# Controller.net
KiCad netlist of a schematic drawn in Altium Designer
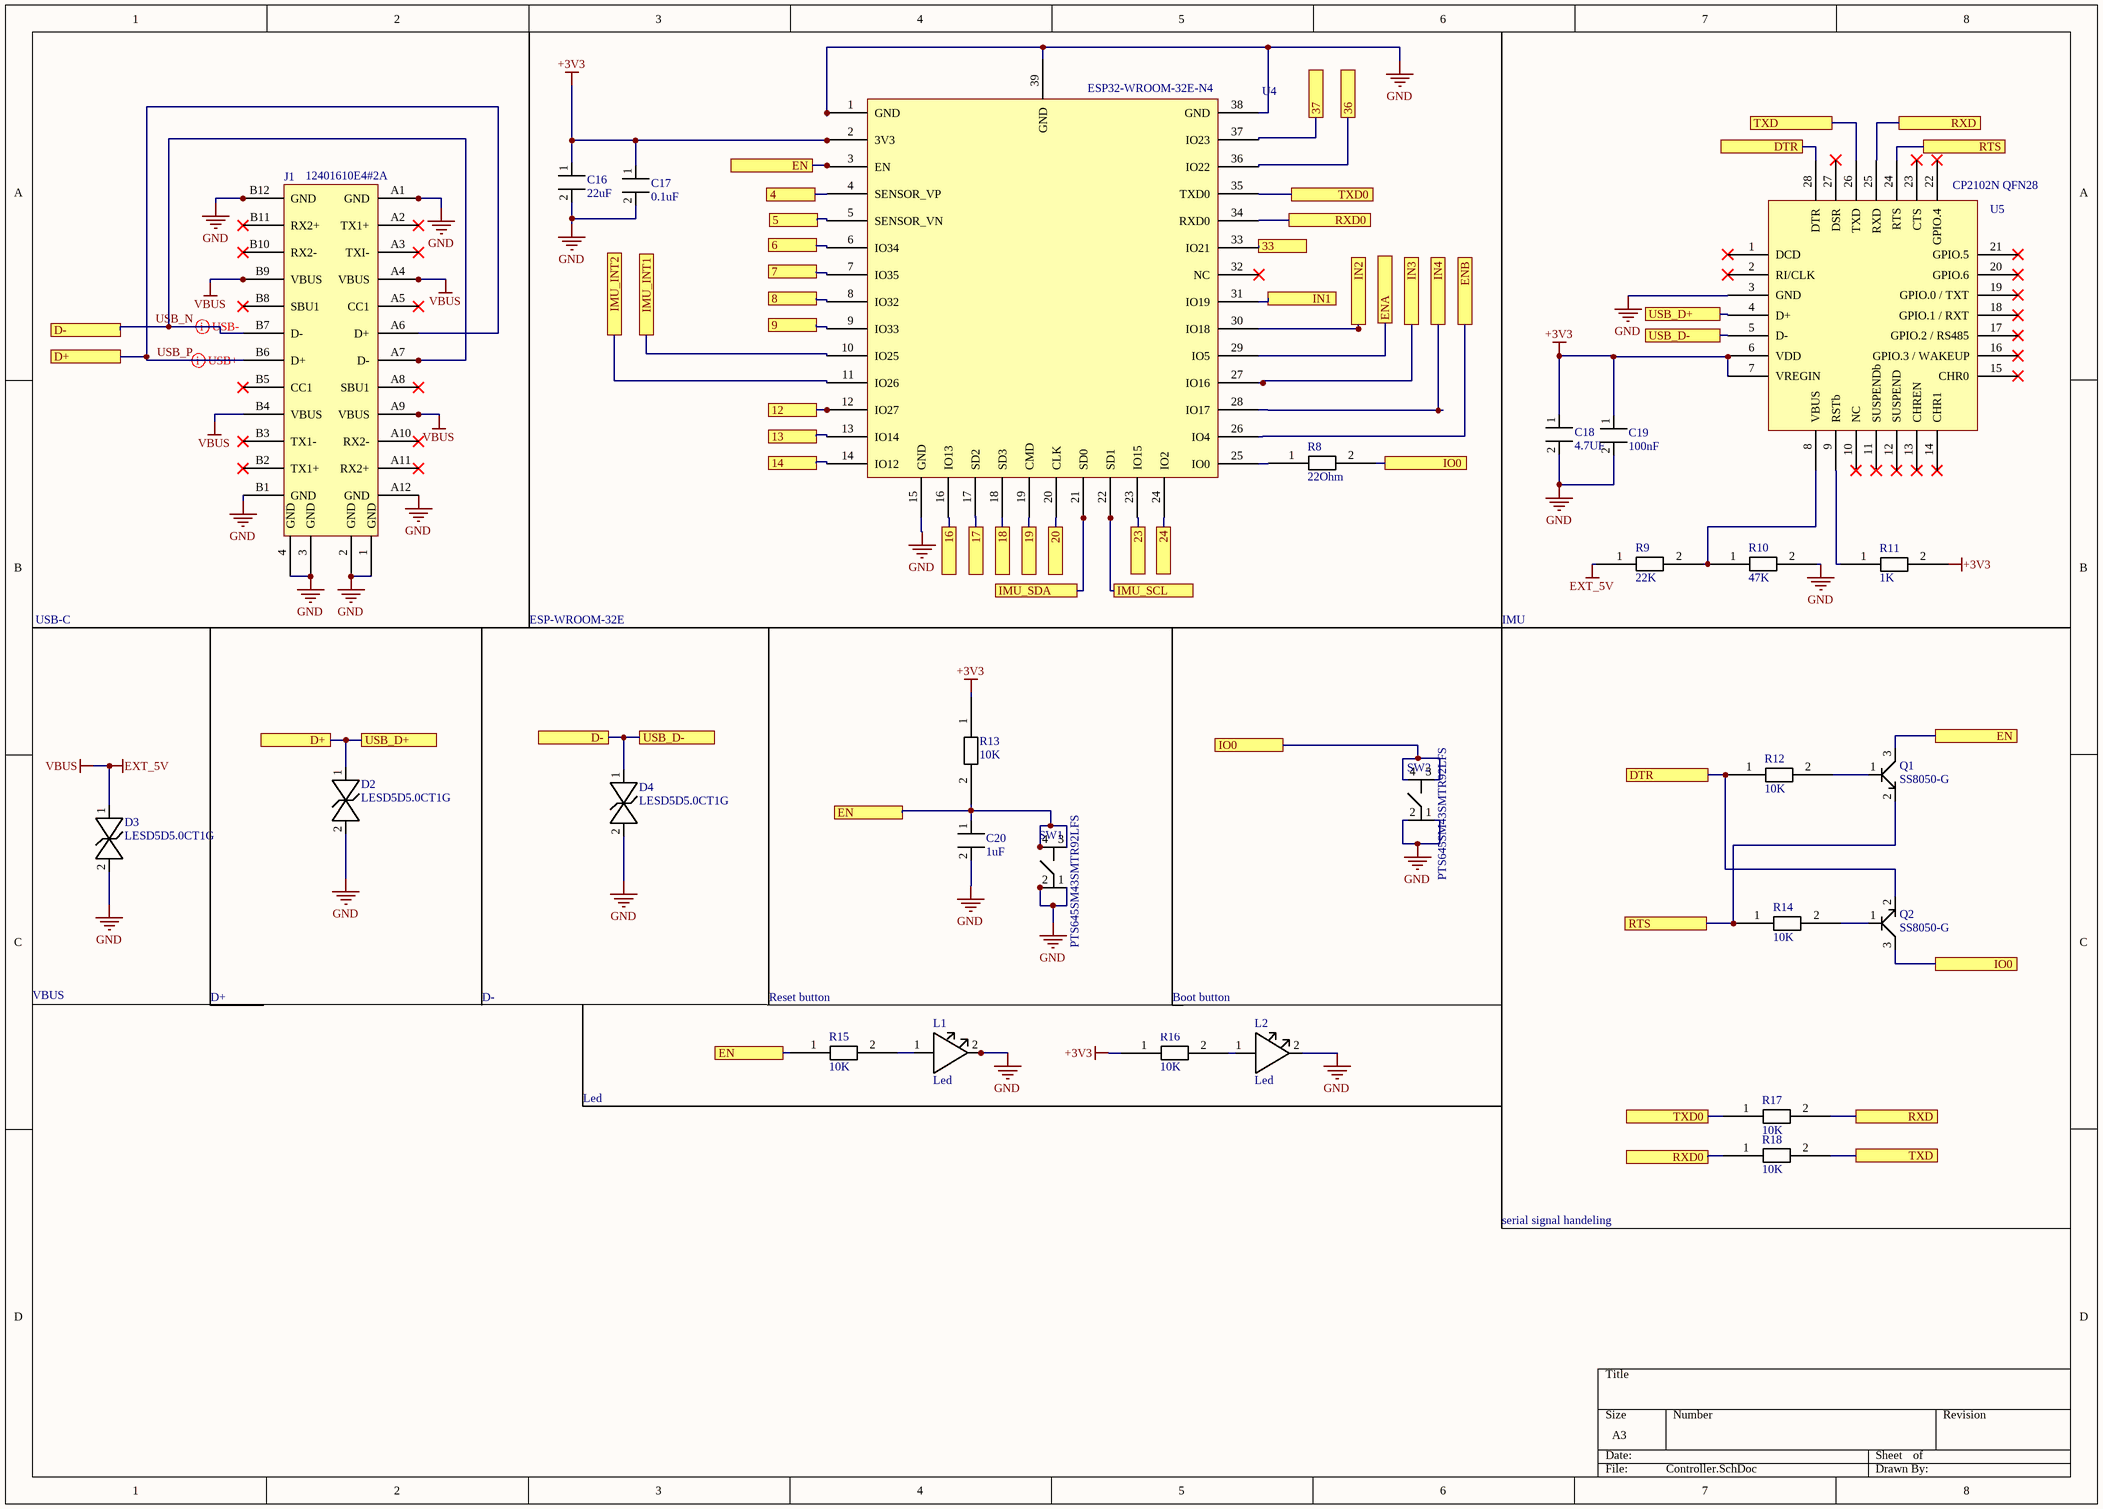
[diagram p0: Controller.SchDoc]

(export (version "E")
  (design (tool "Eeschema 10.0.6"))
  (components
    (comp (ref "C16") (value "22uF") (footprint "Condo") (libsource (lib "Schlib1") (part "CAPA")))
    (comp (ref "C17") (value "0.1uF") (footprint "Condo") (libsource (lib "Schlib1") (part "CAPA")))
    (comp (ref "C18") (value "4.7UF") (footprint "Condo") (libsource (lib "Schlib1") (part "CAPA")))
    (comp (ref "C19") (value "100nF") (footprint "Condo") (libsource (lib "Schlib1") (part "CAPA")))
    (comp (ref "C20") (value "1uF") (footprint "Condo") (libsource (lib "Schlib1") (part "CAPA")))
    (comp (ref "D2")
      (value "LESD5D5.0CT1G")
      (footprint "LESD5D5.0CT1G")
      (libsource (lib "Schlib1") (part "LESD5D5.0CT1G"))
    )
    (comp (ref "D3")
      (value "LESD5D5.0CT1G")
      (footprint "LESD5D5.0CT1G")
      (libsource (lib "Schlib1") (part "LESD5D5.0CT1G"))
    )
    (comp (ref "D4")
      (value "LESD5D5.0CT1G")
      (footprint "LESD5D5.0CT1G")
      (libsource (lib "Schlib1") (part "LESD5D5.0CT1G"))
    )
    (comp (ref "J1")
      (value "12401610E4#2A")
      (footprint "105450-0101")
      (libsource (lib "Schlib1") (part "12401610E4#2A"))
    )
    (comp (ref "L1") (value "Led") (footprint "LED") (libsource (lib "Schlib1") (part "Led")))
    (comp (ref "L2") (value "Led") (footprint "LED") (libsource (lib "Schlib1") (part "Led")))
    (comp (ref "Q1") (value "SS8050-G") (footprint "SS8050-G") (libsource (lib "Schlib1") (part "SS8050-G")))
    (comp (ref "Q2") (value "SS8050-G") (footprint "SS8050-G") (libsource (lib "Schlib1") (part "SS8050-G")))
    (comp (ref "R8") (value "22Ohm") (footprint "Resistor") (libsource (lib "Schlib1") (part "Resistor")))
    (comp (ref "R9") (value "22K") (footprint "Resistor") (libsource (lib "Schlib1") (part "Resistor")))
    (comp (ref "R10") (value "47K") (footprint "Resistor") (libsource (lib "Schlib1") (part "Resistor")))
    (comp (ref "R11") (value "1K") (footprint "Resistor") (libsource (lib "Schlib1") (part "Resistor")))
    (comp (ref "R12") (value "10K") (footprint "Resistor") (libsource (lib "Schlib1") (part "Resistor")))
    (comp (ref "R13") (value "10K") (footprint "Resistor") (libsource (lib "Schlib1") (part "Resistor")))
    (comp (ref "R14") (value "10K") (footprint "Resistor") (libsource (lib "Schlib1") (part "Resistor")))
    (comp (ref "R15") (value "10K") (footprint "Resistor") (libsource (lib "Schlib1") (part "Resistor")))
    (comp (ref "R16") (value "10K") (footprint "Resistor") (libsource (lib "Schlib1") (part "Resistor")))
    (comp (ref "R17") (value "10K") (footprint "Resistor") (libsource (lib "Schlib1") (part "Resistor")))
    (comp (ref "R18") (value "10K") (footprint "Resistor") (libsource (lib "Schlib1") (part "Resistor")))
    (comp (ref "SW1")
      (value "PTS645SM43SMTR92LFS")
      (footprint "PTS645SM43SMTR92LFS")
      (libsource (lib "Schlib1") (part "PTS645SM43SMTR92LFS"))
    )
    (comp (ref "SW2")
      (value "PTS645SM43SMTR92LFS")
      (footprint "PTS645SM43SMTR92LFS")
      (libsource (lib "Schlib1") (part "PTS645SM43SMTR92LFS"))
    )
    (comp (ref "U4")
      (value "ESP32-WROOM-32E-N4")
      (footprint "ESP32-WROOM-32E")
      (libsource (lib "Schlib1") (part "ESP32-WROOM-32E-N4"))
    )
    (comp (ref "U5")
      (value "CP2102N QFN28")
      (footprint "cp2102")
      (libsource (lib "Schlib1") (part "CP2102N QFN28"))
    )
  )
  (nets
    (net (code "1") (name "+3V3") (class "Default")
      (node (ref "C16") (pin "1") (pinfunction "IN_1") (pintype "passive"))
      (node (ref "C17") (pin "1") (pinfunction "IN_1") (pintype "passive"))
      (node (ref "C18") (pin "1") (pinfunction "IN_1") (pintype "passive"))
      (node (ref "C19") (pin "1") (pinfunction "IN_1") (pintype "passive"))
      (node (ref "R11") (pin "2") (pinfunction "2_2") (pintype "passive"))
      (node (ref "R13") (pin "1") (pinfunction "1_1") (pintype "passive"))
      (node (ref "R16") (pin "1") (pinfunction "1_1") (pintype "passive"))
      (node (ref "U4") (pin "2") (pinfunction "3V3_2") (pintype "passive"))
      (node (ref "U5") (pin "6") (pinfunction "VDD_6") (pintype "passive"))
      (node (ref "U5") (pin "7") (pinfunction "VREGIN_7") (pintype "passive"))
    )
    (net (code "2") (name "/4") (class "Default")
      (node (ref "U4") (pin "4") (pinfunction "SENSOR_VP_4") (pintype "passive"))
    )
    (net (code "3") (name "/5") (class "Default")
      (node (ref "U4") (pin "5") (pinfunction "SENSOR_VN_5") (pintype "passive"))
    )
    (net (code "4") (name "/6") (class "Default")
      (node (ref "U4") (pin "6") (pinfunction "IO34_6") (pintype "passive"))
    )
    (net (code "5") (name "/7") (class "Default")
      (node (ref "U4") (pin "7") (pinfunction "IO35_7") (pintype "passive"))
    )
    (net (code "6") (name "/8") (class "Default")
      (node (ref "U4") (pin "8") (pinfunction "IO32_8") (pintype "passive"))
    )
    (net (code "7") (name "/9") (class "Default")
      (node (ref "U4") (pin "9") (pinfunction "IO33_9") (pintype "passive"))
    )
    (net (code "8") (name "/12") (class "Default")
      (node (ref "U4") (pin "12") (pinfunction "IO27_12") (pintype "passive"))
    )
    (net (code "9") (name "/13") (class "Default")
      (node (ref "U4") (pin "13") (pinfunction "IO14_13") (pintype "passive"))
    )
    (net (code "10") (name "/14") (class "Default")
      (node (ref "U4") (pin "14") (pinfunction "IO12_14") (pintype "passive"))
    )
    (net (code "11") (name "/16") (class "Default")
      (node (ref "U4") (pin "16") (pinfunction "IO13_16") (pintype "passive"))
    )
    (net (code "12") (name "/17") (class "Default")
      (node (ref "U4") (pin "17") (pinfunction "SD2_17") (pintype "passive"))
    )
    (net (code "13") (name "/18") (class "Default")
      (node (ref "U4") (pin "18") (pinfunction "SD3_18") (pintype "passive"))
    )
    (net (code "14") (name "/19") (class "Default")
      (node (ref "U4") (pin "19") (pinfunction "CMD_19") (pintype "passive"))
    )
    (net (code "15") (name "/20") (class "Default")
      (node (ref "U4") (pin "20") (pinfunction "CLK_20") (pintype "passive"))
    )
    (net (code "16") (name "/23") (class "Default")
      (node (ref "U4") (pin "23") (pinfunction "IO15_23") (pintype "passive"))
    )
    (net (code "17") (name "/24") (class "Default")
      (node (ref "U4") (pin "24") (pinfunction "IO2_24") (pintype "passive"))
    )
    (net (code "18") (name "/33") (class "Default")
      (node (ref "U4") (pin "33") (pinfunction "IO21_33") (pintype "passive"))
    )
    (net (code "19") (name "/36") (class "Default")
      (node (ref "U4") (pin "36") (pinfunction "IO22_36") (pintype "passive"))
    )
    (net (code "20") (name "/37") (class "Default")
      (node (ref "U4") (pin "37") (pinfunction "IO23_37") (pintype "passive"))
    )
    (net (code "21") (name "/DTR") (class "Default")
      (node (ref "Q2") (pin "2") (pinfunction "2_2") (pintype "passive"))
      (node (ref "R12") (pin "1") (pinfunction "1_1") (pintype "passive"))
      (node (ref "U5") (pin "28") (pinfunction "DTR_28") (pintype "passive"))
    )
    (net (code "22") (name "/EN") (class "Default")
      (node (ref "C20") (pin "1") (pinfunction "IN_1") (pintype "passive"))
      (node (ref "Q1") (pin "3") (pinfunction "3_3") (pintype "passive"))
      (node (ref "R13") (pin "2") (pinfunction "2_2") (pintype "passive"))
      (node (ref "R15") (pin "1") (pinfunction "1_1") (pintype "passive"))
      (node (ref "SW1") (pin "3") (pinfunction "3_3") (pintype "passive"))
      (node (ref "SW1") (pin "4") (pinfunction "4_4") (pintype "passive"))
      (node (ref "U4") (pin "3") (pinfunction "EN_3") (pintype "passive"))
    )
    (net (code "23") (name "/ENA") (class "Default")
      (node (ref "U4") (pin "29") (pinfunction "IO5_29") (pintype "passive"))
    )
    (net (code "24") (name "/ENB") (class "Default")
      (node (ref "U4") (pin "26") (pinfunction "IO4_26") (pintype "passive"))
    )
    (net (code "25") (name "/IMU_INT1") (class "Default")
      (node (ref "U4") (pin "10") (pinfunction "IO25_10") (pintype "passive"))
    )
    (net (code "26") (name "/IMU_INT2") (class "Default")
      (node (ref "U4") (pin "11") (pinfunction "IO26_11") (pintype "passive"))
    )
    (net (code "27") (name "/IMU_SCL") (class "Default")
      (node (ref "U4") (pin "22") (pinfunction "SD1_22") (pintype "passive"))
    )
    (net (code "28") (name "/IMU_SDA") (class "Default")
      (node (ref "U4") (pin "21") (pinfunction "SD0_21") (pintype "passive"))
    )
    (net (code "29") (name "/IN1") (class "Default")
      (node (ref "U4") (pin "31") (pinfunction "IO19_31") (pintype "passive"))
    )
    (net (code "30") (name "/IN2") (class "Default")
      (node (ref "U4") (pin "30") (pinfunction "IO18_30") (pintype "passive"))
    )
    (net (code "31") (name "/IN3") (class "Default")
      (node (ref "U4") (pin "27") (pinfunction "IO16_27") (pintype "passive"))
    )
    (net (code "32") (name "/IN4") (class "Default")
      (node (ref "U4") (pin "28") (pinfunction "IO17_28") (pintype "passive"))
    )
    (net (code "33") (name "/IO0") (class "Default")
      (node (ref "Q2") (pin "3") (pinfunction "3_3") (pintype "passive"))
      (node (ref "R8") (pin "2") (pinfunction "2_2") (pintype "passive"))
      (node (ref "SW2") (pin "3") (pinfunction "3_3") (pintype "passive"))
      (node (ref "SW2") (pin "4") (pinfunction "4_4") (pintype "passive"))
    )
    (net (code "34") (name "/RTS") (class "Default")
      (node (ref "Q1") (pin "2") (pinfunction "2_2") (pintype "passive"))
      (node (ref "R14") (pin "1") (pinfunction "1_1") (pintype "passive"))
      (node (ref "U5") (pin "24") (pinfunction "RTS_24") (pintype "passive"))
    )
    (net (code "35") (name "/RXD") (class "Default")
      (node (ref "R17") (pin "2") (pinfunction "2_2") (pintype "passive"))
      (node (ref "U5") (pin "25") (pinfunction "RXD_25") (pintype "passive"))
    )
    (net (code "36") (name "/RXD0") (class "Default")
      (node (ref "R18") (pin "1") (pinfunction "1_1") (pintype "passive"))
      (node (ref "U4") (pin "34") (pinfunction "RXD0_34") (pintype "passive"))
    )
    (net (code "37") (name "/TXD") (class "Default")
      (node (ref "R18") (pin "2") (pinfunction "2_2") (pintype "passive"))
      (node (ref "U5") (pin "26") (pinfunction "TXD_26") (pintype "passive"))
    )
    (net (code "38") (name "/TXD0") (class "Default")
      (node (ref "R17") (pin "1") (pinfunction "1_1") (pintype "passive"))
      (node (ref "U4") (pin "35") (pinfunction "TXD0_35") (pintype "passive"))
    )
    (net (code "39") (name "/USB_N") (class "Default")
      (node (ref "D4") (pin "1") (pinfunction "vcc_1") (pintype "passive"))
      (node (ref "J1") (pin "A7") (pinfunction "D-_A7") (pintype "passive"))
      (node (ref "J1") (pin "B7") (pinfunction "D-_B7") (pintype "passive"))
      (node (ref "U5") (pin "5") (pinfunction "D-_5") (pintype "passive"))
    )
    (net (code "40") (name "/USB_P") (class "Default")
      (node (ref "D2") (pin "1") (pinfunction "vcc_1") (pintype "passive"))
      (node (ref "J1") (pin "A6") (pinfunction "D+_A6") (pintype "passive"))
      (node (ref "J1") (pin "B6") (pinfunction "D+_B6") (pintype "passive"))
      (node (ref "U5") (pin "4") (pinfunction "D+_4") (pintype "passive"))
    )
    (net (code "41") (name "EXT_5V") (class "Default")
      (node (ref "D3") (pin "1") (pinfunction "vcc_1") (pintype "passive"))
      (node (ref "J1") (pin "A4") (pinfunction "VBUS_A4") (pintype "passive"))
      (node (ref "J1") (pin "A9") (pinfunction "VBUS_A9") (pintype "passive"))
      (node (ref "J1") (pin "B4") (pinfunction "VBUS_B4") (pintype "passive"))
      (node (ref "J1") (pin "B9") (pinfunction "VBUS_B9") (pintype "passive"))
      (node (ref "R9") (pin "1") (pinfunction "1_1") (pintype "passive"))
    )
    (net (code "42") (name "GND") (class "Default")
      (node (ref "C16") (pin "2") (pinfunction "OUT_2") (pintype "passive"))
      (node (ref "C17") (pin "2") (pinfunction "OUT_2") (pintype "passive"))
      (node (ref "C18") (pin "2") (pinfunction "OUT_2") (pintype "passive"))
      (node (ref "C19") (pin "2") (pinfunction "OUT_2") (pintype "passive"))
      (node (ref "C20") (pin "2") (pinfunction "OUT_2") (pintype "passive"))
      (node (ref "D2") (pin "2") (pinfunction "gnd_2") (pintype "passive"))
      (node (ref "D3") (pin "2") (pinfunction "gnd_2") (pintype "passive"))
      (node (ref "D4") (pin "2") (pinfunction "gnd_2") (pintype "passive"))
      (node (ref "J1") (pin "1") (pinfunction "GND_1") (pintype "passive"))
      (node (ref "J1") (pin "2") (pinfunction "GND_2") (pintype "passive"))
      (node (ref "J1") (pin "3") (pinfunction "GND_3") (pintype "passive"))
      (node (ref "J1") (pin "4") (pinfunction "GND_4") (pintype "passive"))
      (node (ref "J1") (pin "A1") (pinfunction "GND_A1") (pintype "passive"))
      (node (ref "J1") (pin "A12") (pinfunction "GND_A12") (pintype "passive"))
      (node (ref "J1") (pin "B1") (pinfunction "GND_B1") (pintype "passive"))
      (node (ref "J1") (pin "B12") (pinfunction "GND_B12") (pintype "passive"))
      (node (ref "L1") (pin "2") (pinfunction "2_2") (pintype "passive"))
      (node (ref "L2") (pin "2") (pinfunction "2_2") (pintype "passive"))
      (node (ref "R10") (pin "2") (pinfunction "2_2") (pintype "passive"))
      (node (ref "SW1") (pin "1") (pinfunction "1_1") (pintype "passive"))
      (node (ref "SW1") (pin "2") (pinfunction "2_2") (pintype "passive"))
      (node (ref "SW2") (pin "1") (pinfunction "1_1") (pintype "passive"))
      (node (ref "SW2") (pin "2") (pinfunction "2_2") (pintype "passive"))
      (node (ref "U4") (pin "1") (pinfunction "GND_1") (pintype "passive"))
      (node (ref "U4") (pin "15") (pinfunction "GND_15") (pintype "passive"))
      (node (ref "U4") (pin "38") (pinfunction "GND_38") (pintype "passive"))
      (node (ref "U4") (pin "39") (pinfunction "GND_39") (pintype "passive"))
      (node (ref "U5") (pin "3") (pinfunction "GND_3") (pintype "passive"))
    )
    (net (code "43") (name "Net-(L1-Pad1)") (class "Default")
      (node (ref "L1") (pin "1") (pinfunction "1_1") (pintype "passive"))
      (node (ref "R15") (pin "2") (pinfunction "2_2") (pintype "passive"))
    )
    (net (code "44") (name "Net-(L2-Pad1)") (class "Default")
      (node (ref "L2") (pin "1") (pinfunction "1_1") (pintype "passive"))
      (node (ref "R16") (pin "2") (pinfunction "2_2") (pintype "passive"))
    )
    (net (code "45") (name "Net-(Q1-Pad1)") (class "Default")
      (node (ref "Q1") (pin "1") (pinfunction "1_1") (pintype "passive"))
      (node (ref "R12") (pin "2") (pinfunction "2_2") (pintype "passive"))
    )
    (net (code "46") (name "Net-(Q2-Pad1)") (class "Default")
      (node (ref "Q2") (pin "1") (pinfunction "1_1") (pintype "passive"))
      (node (ref "R14") (pin "2") (pinfunction "2_2") (pintype "passive"))
    )
    (net (code "47") (name "Net-(U4-IO0)") (class "Default")
      (node (ref "R8") (pin "1") (pinfunction "1_1") (pintype "passive"))
      (node (ref "U4") (pin "25") (pinfunction "IO0_25") (pintype "passive"))
    )
    (net (code "48") (name "Net-(U5-RSTb)") (class "Default")
      (node (ref "R11") (pin "1") (pinfunction "1_1") (pintype "passive"))
      (node (ref "U5") (pin "9") (pinfunction "RSTb_9") (pintype "passive"))
    )
    (net (code "49") (name "Net-(U5-VBUS)") (class "Default")
      (node (ref "R10") (pin "1") (pinfunction "1_1") (pintype "passive"))
      (node (ref "R9") (pin "2") (pinfunction "2_2") (pintype "passive"))
      (node (ref "U5") (pin "8") (pinfunction "VBUS_8") (pintype "passive"))
    )
    (net (code "50") (name "unconnected-(J1-CC1-PadA5)") (class "Default")
      (node (ref "J1") (pin "A5") (pinfunction "CC1_A5") (pintype "passive+no_connect"))
    )
    (net (code "51") (name "unconnected-(J1-CC1-PadB5)") (class "Default")
      (node (ref "J1") (pin "B5") (pinfunction "CC1_B5") (pintype "passive+no_connect"))
    )
    (net (code "52") (name "unconnected-(J1-RX2+-PadA11)") (class "Default")
      (node (ref "J1") (pin "A11") (pinfunction "RX2+_A11") (pintype "passive+no_connect"))
    )
    (net (code "53") (name "unconnected-(J1-RX2+-PadB11)") (class "Default")
      (node (ref "J1") (pin "B11") (pinfunction "RX2+_B11") (pintype "passive+no_connect"))
    )
    (net (code "54") (name "unconnected-(J1-RX2--PadA10)") (class "Default")
      (node (ref "J1") (pin "A10") (pinfunction "RX2-_A10") (pintype "passive+no_connect"))
    )
    (net (code "55") (name "unconnected-(J1-RX2--PadB10)") (class "Default")
      (node (ref "J1") (pin "B10") (pinfunction "RX2-_B10") (pintype "passive+no_connect"))
    )
    (net (code "56") (name "unconnected-(J1-SBU1-PadA8)") (class "Default")
      (node (ref "J1") (pin "A8") (pinfunction "SBU1_A8") (pintype "passive+no_connect"))
    )
    (net (code "57") (name "unconnected-(J1-SBU1-PadB8)") (class "Default")
      (node (ref "J1") (pin "B8") (pinfunction "SBU1_B8") (pintype "passive+no_connect"))
    )
    (net (code "58") (name "unconnected-(J1-TX1+-PadA2)") (class "Default")
      (node (ref "J1") (pin "A2") (pinfunction "TX1+_A2") (pintype "passive+no_connect"))
    )
    (net (code "59") (name "unconnected-(J1-TX1+-PadB2)") (class "Default")
      (node (ref "J1") (pin "B2") (pinfunction "TX1+_B2") (pintype "passive+no_connect"))
    )
    (net (code "60") (name "unconnected-(J1-TX1--PadB3)") (class "Default")
      (node (ref "J1") (pin "B3") (pinfunction "TX1-_B3") (pintype "passive+no_connect"))
    )
    (net (code "61") (name "unconnected-(J1-TXI--PadA3)") (class "Default")
      (node (ref "J1") (pin "A3") (pinfunction "TXI-_A3") (pintype "passive+no_connect"))
    )
    (net (code "62") (name "unconnected-(U4-NC-Pad32)") (class "Default")
      (node (ref "U4") (pin "32") (pinfunction "NC_32") (pintype "passive+no_connect"))
    )
    (net (code "63") (name "unconnected-(U5-CHR0-Pad15)") (class "Default")
      (node (ref "U5") (pin "15") (pinfunction "CHR0_15") (pintype "passive+no_connect"))
    )
    (net (code "64") (name "unconnected-(U5-CHR1-Pad14)") (class "Default")
      (node (ref "U5") (pin "14") (pinfunction "CHR1_14") (pintype "passive+no_connect"))
    )
    (net (code "65") (name "unconnected-(U5-CHREN-Pad13)") (class "Default")
      (node (ref "U5") (pin "13") (pinfunction "CHREN_13") (pintype "passive+no_connect"))
    )
    (net (code "66") (name "unconnected-(U5-CTS-Pad23)") (class "Default")
      (node (ref "U5") (pin "23") (pinfunction "CTS_23") (pintype "passive+no_connect"))
    )
    (net (code "67") (name "unconnected-(U5-DCD-Pad1)") (class "Default")
      (node (ref "U5") (pin "1") (pinfunction "DCD_1") (pintype "passive+no_connect"))
    )
    (net (code "68") (name "unconnected-(U5-DSR-Pad27)") (class "Default")
      (node (ref "U5") (pin "27") (pinfunction "DSR_27") (pintype "passive+no_connect"))
    )
    (net (code "69") (name "unconnected-(U5-GPIO.0_{slash}_TXT-Pad19)") (class "Default")
      (node (ref "U5") (pin "19") (pinfunction "GPIO.0_/_TXT_19") (pintype "passive+no_connect"))
    )
    (net (code "70") (name "unconnected-(U5-GPIO.1_{slash}_RXT-Pad18)") (class "Default")
      (node (ref "U5") (pin "18") (pinfunction "GPIO.1_/_RXT_18") (pintype "passive+no_connect"))
    )
    (net (code "71") (name "unconnected-(U5-GPIO.2_{slash}_RS485-Pad17)") (class "Default")
      (node (ref "U5") (pin "17") (pinfunction "GPIO.2_/_RS485_17") (pintype "passive+no_connect"))
    )
    (net (code "72") (name "unconnected-(U5-GPIO.3_{slash}_WAKEUP-Pad16)") (class "Default")
      (node (ref "U5") (pin "16") (pinfunction "GPIO.3_/_WAKEUP_16") (pintype "passive+no_connect"))
    )
    (net (code "73") (name "unconnected-(U5-GPIO.4-Pad22)") (class "Default")
      (node (ref "U5") (pin "22") (pinfunction "GPIO.4_22") (pintype "passive+no_connect"))
    )
    (net (code "74") (name "unconnected-(U5-GPIO.5-Pad21)") (class "Default")
      (node (ref "U5") (pin "21") (pinfunction "GPIO.5_21") (pintype "passive+no_connect"))
    )
    (net (code "75") (name "unconnected-(U5-GPIO.6-Pad20)") (class "Default")
      (node (ref "U5") (pin "20") (pinfunction "GPIO.6_20") (pintype "passive+no_connect"))
    )
    (net (code "76") (name "unconnected-(U5-NC-Pad10)") (class "Default")
      (node (ref "U5") (pin "10") (pinfunction "NC_10") (pintype "passive+no_connect"))
    )
    (net (code "77") (name "unconnected-(U5-RI{slash}CLK-Pad2)") (class "Default")
      (node (ref "U5") (pin "2") (pinfunction "RI/CLK_2") (pintype "passive+no_connect"))
    )
    (net (code "78") (name "unconnected-(U5-SUSPEND-Pad12)") (class "Default")
      (node (ref "U5") (pin "12") (pinfunction "SUSPEND_12") (pintype "passive+no_connect"))
    )
    (net (code "79") (name "unconnected-(U5-SUSPENDb-Pad11)") (class "Default")
      (node (ref "U5") (pin "11") (pinfunction "SUSPENDb_11") (pintype "passive+no_connect"))
    )
  )
)
